# XBee7.net
KiCad netlist of a schematic drawn in EAGLE
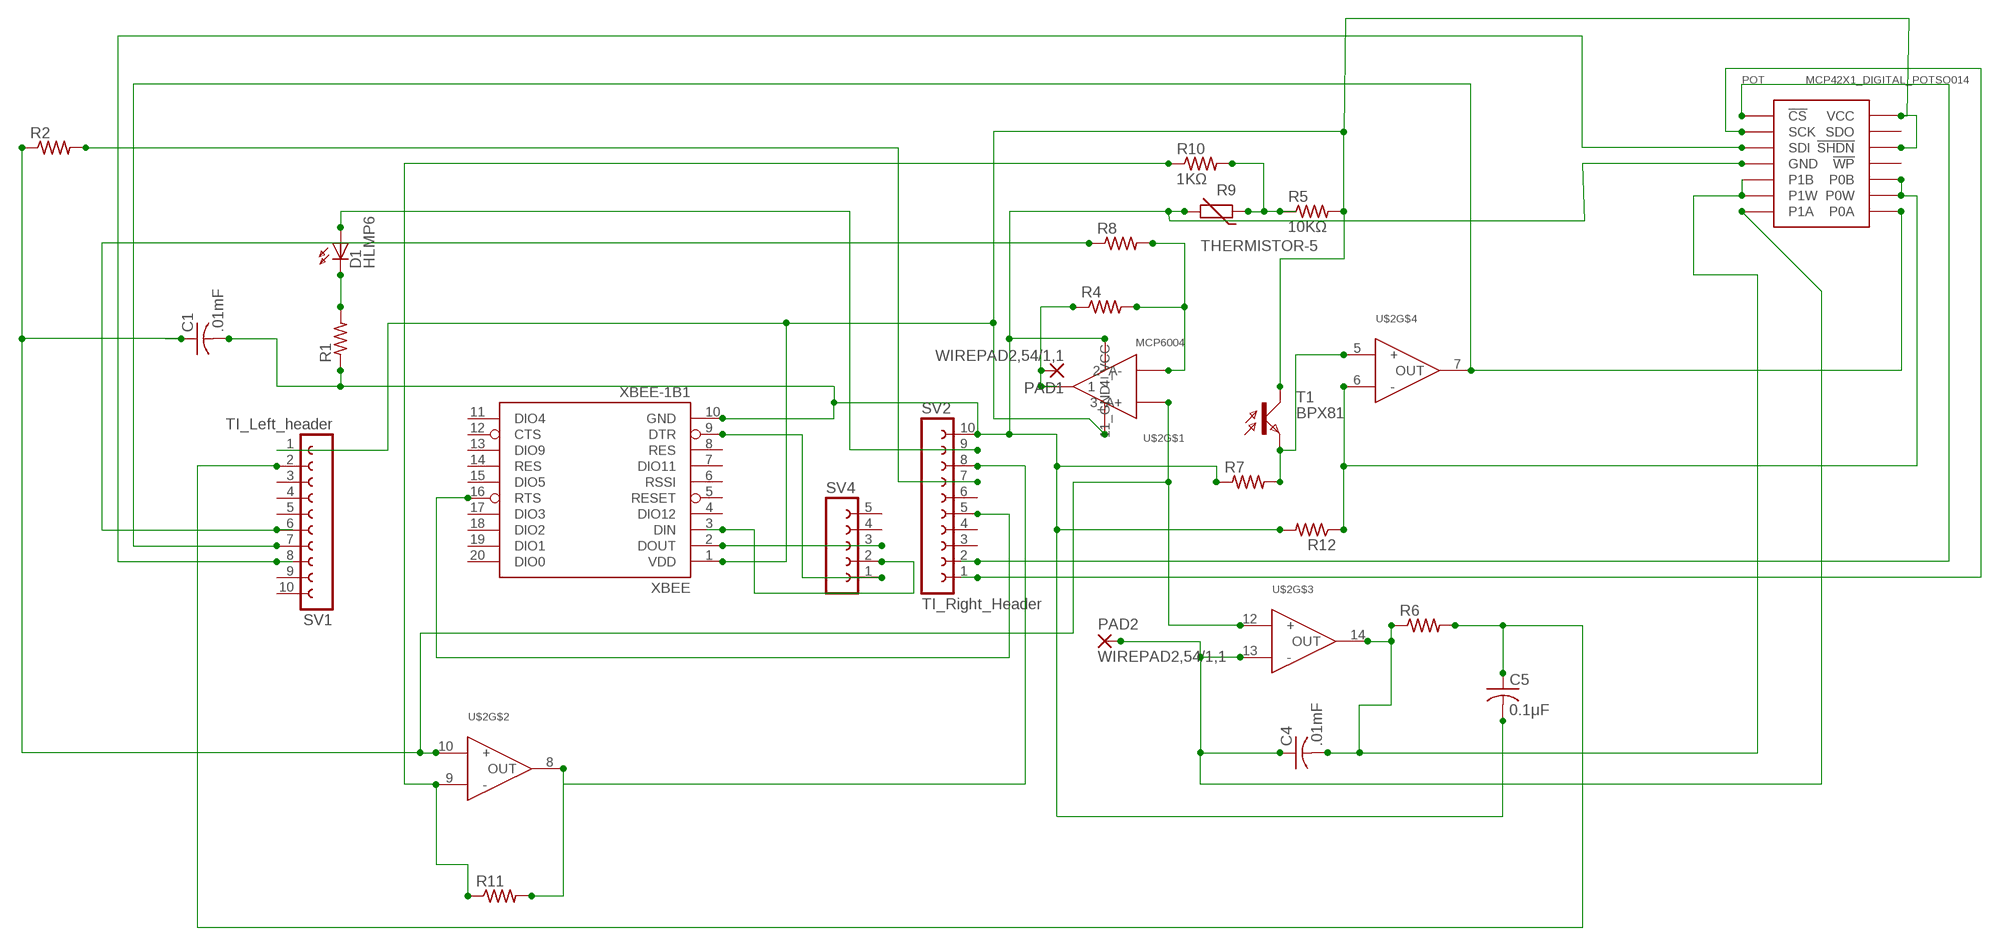
[diagram p0: schematic, sheet 1]

(export (version "E")
  (design (tool "Eeschema 10.0.6"))
  (components
    (comp (ref "C1")
      (value ".01mF")
      (footprint "eagle-import:C0603")
      (libsource (lib "eagle-import") (part "C-USC0603"))
    )
    (comp (ref "C4")
      (value ".01mF")
      (footprint "eagle-import:C0603")
      (libsource (lib "eagle-import") (part "C-USC0603"))
    )
    (comp (ref "C5")
      (value "0.1μF")
      (footprint "eagle-import:C0603")
      (libsource (lib "eagle-import") (part "C-USC0603"))
    )
    (comp (ref "D1")
      (value "HLMP6")
      (footprint "eagle-import:HLMP6")
      (fields (field (name "MF") "AGILENT TECHNOLOGIES") (field (name "MPN") "HLMP-6500"))
      (libsource (lib "eagle-import") (part "HLMP6"))
    )
    (comp (ref "PAD1")
      (value "WIREPAD2,54/1,1")
      (footprint "eagle-import:2,54_1,1")
      (libsource (lib "eagle-import") (part "WIREPAD2,54/1,1"))
    )
    (comp (ref "PAD2")
      (value "WIREPAD2,54/1,1")
      (footprint "eagle-import:2,54_1,1")
      (libsource (lib "eagle-import") (part "WIREPAD2,54/1,1"))
    )
    (comp (ref "POT")
      (value "MCP42X1_DIGITAL_POTSO014")
      (footprint "eagle-import:SO014")
      (libsource (lib "eagle-import") (part "MCP42X1_DIGITAL_POTSO014"))
    )
    (comp (ref "R1")
      (value "R-US_R0603")
      (footprint "eagle-import:R0603")
      (libsource (lib "eagle-import") (part "R-US_R0603"))
    )
    (comp (ref "R2")
      (value "R-US_R0603")
      (footprint "eagle-import:R0603")
      (libsource (lib "eagle-import") (part "R-US_R0603"))
    )
    (comp (ref "R4")
      (value "R-US_R0603")
      (footprint "eagle-import:R0603")
      (libsource (lib "eagle-import") (part "R-US_R0603"))
    )
    (comp (ref "R5")
      (value "10KΩ")
      (footprint "eagle-import:R0603")
      (libsource (lib "eagle-import") (part "R-US_R0603"))
    )
    (comp (ref "R6")
      (value "R-US_R0603")
      (footprint "eagle-import:R0603")
      (libsource (lib "eagle-import") (part "R-US_R0603"))
    )
    (comp (ref "R7")
      (value "R-US_R0603")
      (footprint "eagle-import:R0603")
      (libsource (lib "eagle-import") (part "R-US_R0603"))
    )
    (comp (ref "R8")
      (value "R-US_R0603")
      (footprint "eagle-import:R0603")
      (libsource (lib "eagle-import") (part "R-US_R0603"))
    )
    (comp (ref "R9")
      (value "THERMISTOR-5")
      (footprint "eagle-import:R-5")
      (libsource (lib "eagle-import") (part "THERMISTOR-5"))
    )
    (comp (ref "R10")
      (value "1KΩ")
      (footprint "eagle-import:R0603")
      (libsource (lib "eagle-import") (part "R-US_R0603"))
    )
    (comp (ref "R11")
      (value "R-US_R0603")
      (footprint "eagle-import:R0603")
      (libsource (lib "eagle-import") (part "R-US_R0603"))
    )
    (comp (ref "R12")
      (value "R-US_R0603")
      (footprint "eagle-import:R0603")
      (libsource (lib "eagle-import") (part "R-US_R0603"))
    )
    (comp (ref "SV1")
      (value "TI_Left_header")
      (footprint "eagle-import:FE10")
      (libsource (lib "eagle-import") (part "FE10-1"))
    )
    (comp (ref "SV2")
      (value "TI_Right_Header")
      (footprint "eagle-import:FE10")
      (libsource (lib "eagle-import") (part "FE10-1"))
    )
    (comp (ref "SV4")
      (value "FE05-1")
      (footprint "eagle-import:FE05-1")
      (libsource (lib "eagle-import") (part "FE05-1"))
    )
    (comp (ref "T1")
      (value "BPX81")
      (footprint "eagle-import:BPX81")
      (libsource (lib "eagle-import") (part "BPX81"))
    )
    (comp (ref "U$2")
      (value "MCP6004")
      (footprint "eagle-import:SO014")
      (libsource (lib "eagle-import") (part "MCP6004"))
    )
    (comp (ref "XBEE")
      (value "XBEE-1B1")
      (footprint "eagle-import:XBEE-1")
      (libsource (lib "eagle-import") (part "XBEE-1B1"))
    )
  )
  (nets
    (net (code "1") (name "Net-(C5-Pad1)") (class "Default")
      (node (ref "C5") (pin "1") (pinfunction "1_1") (pintype "passive"))
      (node (ref "R6") (pin "2") (pinfunction "2_2") (pintype "passive"))
      (node (ref "SV1") (pin "2") (pinfunction "2_2") (pintype "passive"))
    )
    (net (code "2") (name "Net-(D1-PadA)") (class "Default")
      (node (ref "D1") (pin "A") (pinfunction "A_A") (pintype "passive"))
      (node (ref "SV2") (pin "9") (pinfunction "9_9") (pintype "passive"))
    )
    (net (code "3") (name "Net-(D1-PadK)") (class "Default")
      (node (ref "D1") (pin "K") (pinfunction "K_K") (pintype "passive"))
      (node (ref "R1") (pin "2") (pinfunction "2_2") (pintype "passive"))
    )
    (net (code "4") (name "Net-(PAD1-P)") (class "Default")
      (node (ref "PAD1") (pin "1") (pinfunction "P_1") (pintype "passive"))
      (node (ref "R4") (pin "1") (pinfunction "1_1") (pintype "passive"))
      (node (ref "U$2") (pin "1") (pinfunction "1_1") (pintype "bidirectional"))
    )
    (net (code "5") (name "Net-(PAD2-P)") (class "Default")
      (node (ref "C4") (pin "1") (pinfunction "1_1") (pintype "passive"))
      (node (ref "PAD2") (pin "1") (pinfunction "P_1") (pintype "passive"))
      (node (ref "POT") (pin "P7") (pinfunction "P1A_P7") (pintype "bidirectional"))
      (node (ref "U$2") (pin "13") (pinfunction "-_13") (pintype "bidirectional"))
    )
    (net (code "6") (name "Net-(POT-GND)") (class "Default")
      (node (ref "C1") (pin "2") (pinfunction "2_2") (pintype "passive"))
      (node (ref "C5") (pin "2") (pinfunction "2_2") (pintype "passive"))
      (node (ref "POT") (pin "P4") (pinfunction "GND_P4") (pintype "bidirectional"))
      (node (ref "R1") (pin "1") (pinfunction "1_1") (pintype "passive"))
      (node (ref "R12") (pin "2") (pinfunction "2_2") (pintype "passive"))
      (node (ref "R7") (pin "1") (pinfunction "1_1") (pintype "passive"))
      (node (ref "R9") (pin "2") (pinfunction "2_2") (pintype "passive"))
      (node (ref "SV2") (pin "10") (pinfunction "10_10") (pintype "passive"))
      (node (ref "U$2") (pin "11") (pinfunction "11_GND_11") (pintype "power_in"))
      (node (ref "XBEE") (pin "10") (pinfunction "GND_10") (pintype "power_in"))
    )
    (net (code "7") (name "Net-(POT-P0A)") (class "Default")
      (node (ref "POT") (pin "P8") (pinfunction "P0A_P8") (pintype "bidirectional"))
      (node (ref "SV1") (pin "7") (pinfunction "7_7") (pintype "passive"))
      (node (ref "U$2") (pin "7") (pinfunction "OUT_7") (pintype "bidirectional"))
    )
    (net (code "8") (name "Net-(POT-P0B)") (class "Default")
      (node (ref "POT") (pin "P10") (pinfunction "P0B_P10") (pintype "bidirectional"))
      (node (ref "POT") (pin "P9") (pinfunction "P0W_P9") (pintype "bidirectional"))
      (node (ref "R12") (pin "1") (pinfunction "1_1") (pintype "passive"))
      (node (ref "U$2") (pin "6") (pinfunction "-_6") (pintype "bidirectional"))
    )
    (net (code "9") (name "Net-(POT-P1B)") (class "Default")
      (node (ref "C4") (pin "2") (pinfunction "2_2") (pintype "passive"))
      (node (ref "POT") (pin "P5") (pinfunction "P1B_P5") (pintype "bidirectional"))
      (node (ref "POT") (pin "P6") (pinfunction "P1W_P6") (pintype "bidirectional"))
      (node (ref "R6") (pin "1") (pinfunction "1_1") (pintype "passive"))
      (node (ref "U$2") (pin "14") (pinfunction "OUT_14") (pintype "bidirectional"))
    )
    (net (code "10") (name "Net-(POT-SCK)") (class "Default")
      (node (ref "POT") (pin "P2") (pinfunction "SCK_P2") (pintype "bidirectional"))
      (node (ref "SV2") (pin "1") (pinfunction "1_1") (pintype "passive"))
    )
    (net (code "11") (name "Net-(POT-SDI)") (class "Default")
      (node (ref "POT") (pin "P3") (pinfunction "SDI_P3") (pintype "bidirectional"))
      (node (ref "SV1") (pin "8") (pinfunction "8_8") (pintype "passive"))
    )
    (net (code "12") (name "Net-(POT-VCC)") (class "Default")
      (node (ref "POT") (pin "P12") (pinfunction "~{SHDN}_P12") (pintype "bidirectional"))
      (node (ref "POT") (pin "P14") (pinfunction "VCC_P14") (pintype "bidirectional"))
      (node (ref "R5") (pin "2") (pinfunction "2_2") (pintype "passive"))
      (node (ref "SV1") (pin "1") (pinfunction "1_1") (pintype "passive"))
      (node (ref "T1") (pin "C") (pinfunction "C_C") (pintype "passive"))
      (node (ref "U$2") (pin "4") (pinfunction "4_VCC_4") (pintype "power_in"))
      (node (ref "XBEE") (pin "1") (pinfunction "VDD_1") (pintype "power_in"))
    )
    (net (code "13") (name "Net-(POT-~{CS})") (class "Default")
      (node (ref "POT") (pin "P1") (pinfunction "~{CS}_P1") (pintype "bidirectional"))
      (node (ref "SV2") (pin "2") (pinfunction "2_2") (pintype "passive"))
    )
    (net (code "14") (name "Net-(R2-Pad2)") (class "Default")
      (node (ref "R2") (pin "2") (pinfunction "2_2") (pintype "passive"))
      (node (ref "SV2") (pin "7") (pinfunction "7_7") (pintype "passive"))
    )
    (net (code "15") (name "Net-(R8-Pad1)") (class "Default")
      (node (ref "R8") (pin "1") (pinfunction "1_1") (pintype "passive"))
      (node (ref "SV1") (pin "6") (pinfunction "6_6") (pintype "passive"))
    )
    (net (code "16") (name "Net-(R10-Pad2)") (class "Default")
      (node (ref "R10") (pin "2") (pinfunction "2_2") (pintype "passive"))
      (node (ref "R5") (pin "1") (pinfunction "1_1") (pintype "passive"))
      (node (ref "R9") (pin "1") (pinfunction "1_1") (pintype "passive"))
    )
    (net (code "17") (name "Net-(U$2A-2_A-)") (class "Default")
      (node (ref "R4") (pin "2") (pinfunction "2_2") (pintype "passive"))
      (node (ref "R8") (pin "2") (pinfunction "2_2") (pintype "passive"))
      (node (ref "U$2") (pin "2") (pinfunction "2_A-_2") (pintype "bidirectional"))
    )
    (net (code "18") (name "Net-(U$2A-3_A+)") (class "Default")
      (node (ref "C1") (pin "1") (pinfunction "1_1") (pintype "passive"))
      (node (ref "R2") (pin "1") (pinfunction "1_1") (pintype "passive"))
      (node (ref "U$2") (pin "10") (pinfunction "+_10") (pintype "bidirectional"))
      (node (ref "U$2") (pin "12") (pinfunction "+_12") (pintype "bidirectional"))
      (node (ref "U$2") (pin "3") (pinfunction "3_A+_3") (pintype "bidirectional"))
    )
    (net (code "19") (name "Net-(U$2B--)") (class "Default")
      (node (ref "R10") (pin "1") (pinfunction "1_1") (pintype "passive"))
      (node (ref "R11") (pin "1") (pinfunction "1_1") (pintype "passive"))
      (node (ref "U$2") (pin "9") (pinfunction "-_9") (pintype "bidirectional"))
    )
    (net (code "20") (name "Net-(U$2B-OUT)") (class "Default")
      (node (ref "R11") (pin "2") (pinfunction "2_2") (pintype "passive"))
      (node (ref "SV2") (pin "8") (pinfunction "8_8") (pintype "passive"))
      (node (ref "U$2") (pin "8") (pinfunction "OUT_8") (pintype "bidirectional"))
    )
    (net (code "21") (name "Net-(U$2D-+)") (class "Default")
      (node (ref "R7") (pin "2") (pinfunction "2_2") (pintype "passive"))
      (node (ref "T1") (pin "E") (pinfunction "E_E") (pintype "passive"))
      (node (ref "U$2") (pin "5") (pinfunction "+_5") (pintype "bidirectional"))
    )
    (net (code "22") (name "Net-(XBEE-DIN)") (class "Default")
      (node (ref "SV4") (pin "2") (pinfunction "2_2") (pintype "passive"))
      (node (ref "XBEE") (pin "3") (pinfunction "DIN_3") (pintype "input"))
    )
    (net (code "23") (name "Net-(XBEE-DOUT)") (class "Default")
      (node (ref "SV4") (pin "3") (pinfunction "3_3") (pintype "passive"))
      (node (ref "XBEE") (pin "2") (pinfunction "DOUT_2") (pintype "output"))
    )
    (net (code "24") (name "Net-(XBEE-DTR)") (class "Default")
      (node (ref "SV4") (pin "1") (pinfunction "1_1") (pintype "passive"))
      (node (ref "XBEE") (pin "9") (pinfunction "DTR_9") (pintype "bidirectional"))
    )
    (net (code "25") (name "Net-(XBEE-RTS)") (class "Default")
      (node (ref "SV2") (pin "5") (pinfunction "5_5") (pintype "passive"))
      (node (ref "XBEE") (pin "16") (pinfunction "RTS_16") (pintype "input"))
    )
    (net (code "26") (name "unconnected-(POT-SDO-PadP13)") (class "Default")
      (node (ref "POT") (pin "P13") (pinfunction "SDO_P13") (pintype "bidirectional"))
    )
    (net (code "27") (name "unconnected-(POT-~{WP}-PadP11)") (class "Default")
      (node (ref "POT") (pin "P11") (pinfunction "~{WP}_P11") (pintype "bidirectional"))
    )
    (net (code "28") (name "unconnected-(SV1-Pad3)") (class "Default")
      (node (ref "SV1") (pin "3") (pinfunction "3_3") (pintype "passive"))
    )
    (net (code "29") (name "unconnected-(SV1-Pad4)") (class "Default")
      (node (ref "SV1") (pin "4") (pinfunction "4_4") (pintype "passive"))
    )
    (net (code "30") (name "unconnected-(SV1-Pad5)") (class "Default")
      (node (ref "SV1") (pin "5") (pinfunction "5_5") (pintype "passive"))
    )
    (net (code "31") (name "unconnected-(SV1-Pad9)") (class "Default")
      (node (ref "SV1") (pin "9") (pinfunction "9_9") (pintype "passive"))
    )
    (net (code "32") (name "unconnected-(SV1-Pad10)") (class "Default")
      (node (ref "SV1") (pin "10") (pinfunction "10_10") (pintype "passive"))
    )
    (net (code "33") (name "unconnected-(SV2-Pad3)") (class "Default")
      (node (ref "SV2") (pin "3") (pinfunction "3_3") (pintype "passive"))
    )
    (net (code "34") (name "unconnected-(SV2-Pad4)") (class "Default")
      (node (ref "SV2") (pin "4") (pinfunction "4_4") (pintype "passive"))
    )
    (net (code "35") (name "unconnected-(SV2-Pad6)") (class "Default")
      (node (ref "SV2") (pin "6") (pinfunction "6_6") (pintype "passive"))
    )
    (net (code "36") (name "unconnected-(SV4-Pad4)") (class "Default")
      (node (ref "SV4") (pin "4") (pinfunction "4_4") (pintype "passive"))
    )
    (net (code "37") (name "unconnected-(SV4-Pad5)") (class "Default")
      (node (ref "SV4") (pin "5") (pinfunction "5_5") (pintype "passive"))
    )
    (net (code "38") (name "unconnected-(XBEE-CTS-Pad12)") (class "Default")
      (node (ref "XBEE") (pin "12") (pinfunction "CTS_12") (pintype "output"))
    )
    (net (code "39") (name "unconnected-(XBEE-DIO0-Pad20)") (class "Default")
      (node (ref "XBEE") (pin "20") (pinfunction "DIO0_20") (pintype "bidirectional"))
    )
    (net (code "40") (name "unconnected-(XBEE-DIO1-Pad19)") (class "Default")
      (node (ref "XBEE") (pin "19") (pinfunction "DIO1_19") (pintype "bidirectional"))
    )
    (net (code "41") (name "unconnected-(XBEE-DIO2-Pad18)") (class "Default")
      (node (ref "XBEE") (pin "18") (pinfunction "DIO2_18") (pintype "bidirectional"))
    )
    (net (code "42") (name "unconnected-(XBEE-DIO3-Pad17)") (class "Default")
      (node (ref "XBEE") (pin "17") (pinfunction "DIO3_17") (pintype "bidirectional"))
    )
    (net (code "43") (name "unconnected-(XBEE-DIO4-Pad11)") (class "Default")
      (node (ref "XBEE") (pin "11") (pinfunction "DIO4_11") (pintype "bidirectional"))
    )
    (net (code "44") (name "unconnected-(XBEE-DIO5-Pad15)") (class "Default")
      (node (ref "XBEE") (pin "15") (pinfunction "DIO5_15") (pintype "bidirectional"))
    )
    (net (code "45") (name "unconnected-(XBEE-DIO9-Pad13)") (class "Default")
      (node (ref "XBEE") (pin "13") (pinfunction "DIO9_13") (pintype "bidirectional"))
    )
    (net (code "46") (name "unconnected-(XBEE-DIO11-Pad7)") (class "Default")
      (node (ref "XBEE") (pin "7") (pinfunction "DIO11_7") (pintype "bidirectional"))
    )
    (net (code "47") (name "unconnected-(XBEE-DIO12-Pad4)") (class "Default")
      (node (ref "XBEE") (pin "4") (pinfunction "DIO12_4") (pintype "bidirectional"))
    )
    (net (code "48") (name "unconnected-(XBEE-RES-Pad8)") (class "Default")
      (node (ref "XBEE") (pin "8") (pinfunction "RES_8") (pintype "bidirectional"))
    )
    (net (code "49") (name "unconnected-(XBEE-RES-Pad14)") (class "Default")
      (node (ref "XBEE") (pin "14") (pinfunction "RES_14") (pintype "bidirectional"))
    )
    (net (code "50") (name "unconnected-(XBEE-RESET-Pad5)") (class "Default")
      (node (ref "XBEE") (pin "5") (pinfunction "RESET_5") (pintype "input"))
    )
    (net (code "51") (name "unconnected-(XBEE-RSSI-Pad6)") (class "Default")
      (node (ref "XBEE") (pin "6") (pinfunction "RSSI_6") (pintype "bidirectional"))
    )
  )
)
